# new_main.net
KiCad netlist of a schematic drawn in EAGLE
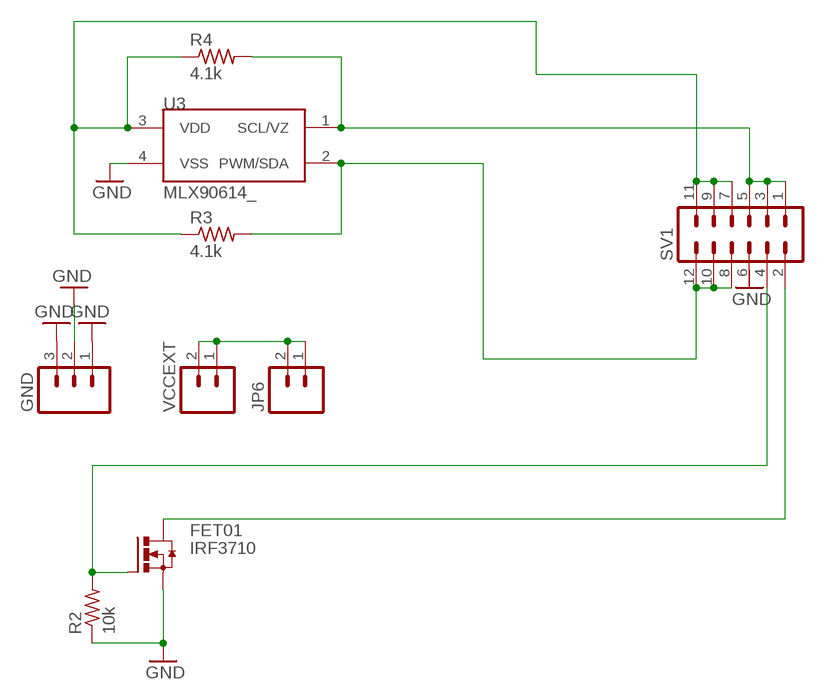
[diagram p0: schematic, sheet 1]

(export (version "E")
  (design (tool "Eeschema 10.0.6"))
  (components
    (comp (ref "FET01")
      (value "IRF3710")
      (footprint "eagle-import:TO220AH")
      (libsource (lib "eagle-import") (part "IRF3704"))
    )
    (comp (ref "GND")
      (value "M03LONGPADS")
      (footprint "eagle-import:1X03_LONGPADS")
      (libsource (lib "eagle-import") (part "M03LONGPADS"))
    )
    (comp (ref "JP6")
      (value "M02LOCK_LONGPADS")
      (footprint "eagle-import:1X02_LOCK_LONGPADS")
      (libsource (lib "eagle-import") (part "M02LOCK_LONGPADS"))
    )
    (comp (ref "R2")
      (value "10k")
      (footprint "eagle-import:0207_7")
      (libsource (lib "eagle-import") (part "R-US_0207/7"))
    )
    (comp (ref "R3")
      (value "4.1k")
      (footprint "eagle-import:0204_5")
      (libsource (lib "eagle-import") (part "R-US_0204/5"))
    )
    (comp (ref "R4")
      (value "4.1k")
      (footprint "eagle-import:0204_5")
      (libsource (lib "eagle-import") (part "R-US_0204/5"))
    )
    (comp (ref "SV1")
      (value "MA06-2")
      (footprint "eagle-import:MA06-2")
      (libsource (lib "eagle-import") (part "MA06-2"))
    )
    (comp (ref "U3")
      (value "MLX90614_")
      (footprint "eagle-import:TO-39")
      (libsource (lib "eagle-import") (part "MLX90614_"))
    )
    (comp (ref "VCCEXT")
      (value "M02LOCK_LONGPADS")
      (footprint "eagle-import:1X02_LOCK_LONGPADS")
      (libsource (lib "eagle-import") (part "M02LOCK_LONGPADS"))
    )
  )
  (nets
    (net (code "1") (name "GND") (class "Default")
      (node (ref "FET01") (pin "E") (pinfunction "S_E") (pintype "passive"))
      (node (ref "GND") (pin "1") (pinfunction "1_1") (pintype "passive"))
      (node (ref "GND") (pin "2") (pinfunction "2_2") (pintype "passive"))
      (node (ref "GND") (pin "3") (pinfunction "3_3") (pintype "passive"))
      (node (ref "R2") (pin "1") (pinfunction "1_1") (pintype "passive"))
      (node (ref "U3") (pin "4") (pinfunction "VSS_4") (pintype "bidirectional"))
    )
    (net (code "2") (name "Net-(FET01-D)") (class "Default")
      (node (ref "FET01") (pin "C") (pinfunction "D_C") (pintype "passive"))
      (node (ref "SV1") (pin "2") (pinfunction "2_2") (pintype "passive"))
    )
    (net (code "3") (name "Net-(FET01-G)") (class "Default")
      (node (ref "FET01") (pin "B") (pinfunction "G_B") (pintype "passive"))
      (node (ref "R2") (pin "2") (pinfunction "2_2") (pintype "passive"))
      (node (ref "SV1") (pin "4") (pinfunction "4_4") (pintype "passive"))
    )
    (net (code "4") (name "Net-(JP6-Pad1)") (class "Default")
      (node (ref "JP6") (pin "1") (pinfunction "1_1") (pintype "passive"))
      (node (ref "JP6") (pin "2") (pinfunction "2_2") (pintype "passive"))
      (node (ref "VCCEXT") (pin "1") (pinfunction "1_1") (pintype "passive"))
      (node (ref "VCCEXT") (pin "2") (pinfunction "2_2") (pintype "passive"))
    )
    (net (code "5") (name "Net-(U3-PWM{slash}SDA)") (class "Default")
      (node (ref "R3") (pin "2") (pinfunction "2_2") (pintype "passive"))
      (node (ref "SV1") (pin "10") (pinfunction "10_10") (pintype "passive"))
      (node (ref "SV1") (pin "12") (pinfunction "12_12") (pintype "passive"))
      (node (ref "SV1") (pin "8") (pinfunction "8_8") (pintype "passive"))
      (node (ref "U3") (pin "2") (pinfunction "PWM/SDA_2") (pintype "bidirectional"))
    )
    (net (code "6") (name "Net-(U3-SCL{slash}VZ)") (class "Default")
      (node (ref "R4") (pin "2") (pinfunction "2_2") (pintype "passive"))
      (node (ref "SV1") (pin "1") (pinfunction "1_1") (pintype "passive"))
      (node (ref "SV1") (pin "3") (pinfunction "3_3") (pintype "passive"))
      (node (ref "SV1") (pin "5") (pinfunction "5_5") (pintype "passive"))
      (node (ref "U3") (pin "1") (pinfunction "SCL/VZ_1") (pintype "bidirectional"))
    )
    (net (code "7") (name "Net-(U3-VDD)") (class "Default")
      (node (ref "R3") (pin "1") (pinfunction "1_1") (pintype "passive"))
      (node (ref "R4") (pin "1") (pinfunction "1_1") (pintype "passive"))
      (node (ref "SV1") (pin "11") (pinfunction "11_11") (pintype "passive"))
      (node (ref "SV1") (pin "7") (pinfunction "7_7") (pintype "passive"))
      (node (ref "SV1") (pin "9") (pinfunction "9_9") (pintype "passive"))
      (node (ref "U3") (pin "3") (pinfunction "VDD_3") (pintype "bidirectional"))
    )
    (net (code "8") (name "unconnected-(SV1-Pad6)") (class "Default")
      (node (ref "SV1") (pin "6") (pinfunction "6_6") (pintype "passive"))
    )
  )
)
